# BSPD_Test_Board.net
KiCad netlist of a schematic drawn in EAGLE
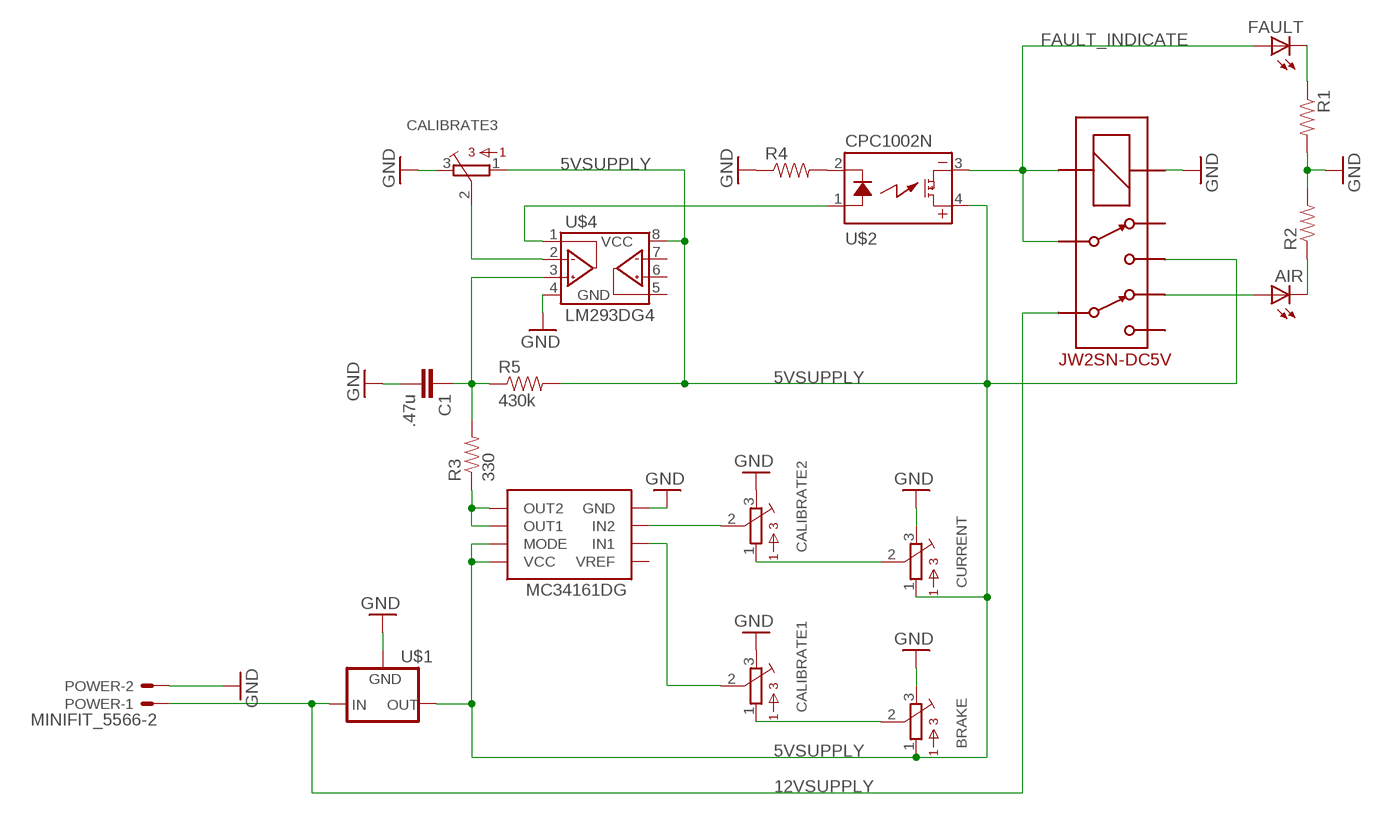
[diagram p0: schematic, sheet 1]

(export (version "E")
  (design (tool "Eeschema 10.0.6"))
  (components
    (comp (ref "AIR")
      (value "LED-5MM")
      (footprint "eagle-import:LED-5MM")
      (libsource (lib "eagle-import") (part "LED-5MM"))
    )
    (comp (ref "BRAKE")
      (value "TRIMPOT_3296C")
      (footprint "eagle-import:TRIMPOT_3296")
      (libsource (lib "eagle-import") (part "TRIMPOT_3296C"))
    )
    (comp (ref "C1")
      (value ".47u")
      (footprint "eagle-import:CAP-PTH-SMALLEZ")
      (libsource (lib "eagle-import") (part "CAPEZ"))
    )
    (comp (ref "CALIBRATE1")
      (value "TRIMPOT_3296C")
      (footprint "eagle-import:TRIMPOT_3296")
      (libsource (lib "eagle-import") (part "TRIMPOT_3296C"))
    )
    (comp (ref "CALIBRATE2")
      (value "TRIMPOT_3296C")
      (footprint "eagle-import:TRIMPOT_3296")
      (libsource (lib "eagle-import") (part "TRIMPOT_3296C"))
    )
    (comp (ref "CALIBRATE3")
      (value "TRIMPOT_3296C")
      (footprint "eagle-import:TRIMPOT_3296")
      (libsource (lib "eagle-import") (part "TRIMPOT_3296C"))
    )
    (comp (ref "CURRENT")
      (value "TRIMPOT_3296C")
      (footprint "eagle-import:TRIMPOT_3296")
      (libsource (lib "eagle-import") (part "TRIMPOT_3296C"))
    )
    (comp (ref "FAULT")
      (value "LED-5MM")
      (footprint "eagle-import:LED-5MM")
      (libsource (lib "eagle-import") (part "LED-5MM"))
    )
    (comp (ref "MC34161DG")
      (value "VOLTAGE_MONITOR_MC34161DG")
      (footprint "eagle-import:SOIC-08")
      (libsource (lib "eagle-import") (part "VOLTAGE_MONITOR_MC34161DG"))
    )
    (comp (ref "POWER")
      (value "MINIFIT_5566-2")
      (footprint "eagle-import:MINIFIT_5566-2")
      (libsource (lib "eagle-import") (part "MINIFIT_5566-2"))
    )
    (comp (ref "R1")
      (value "RESISTOR0805-RES")
      (footprint "eagle-import:0805")
      (libsource (lib "eagle-import") (part "RESISTOR0805-RES"))
    )
    (comp (ref "R2")
      (value "RESISTOR0805-RES")
      (footprint "eagle-import:0805")
      (libsource (lib "eagle-import") (part "RESISTOR0805-RES"))
    )
    (comp (ref "R3")
      (value "330")
      (footprint "eagle-import:0805")
      (libsource (lib "eagle-import") (part "RESISTOR0805-RES"))
    )
    (comp (ref "R4")
      (value "RESISTOR0805-RES")
      (footprint "eagle-import:0805")
      (libsource (lib "eagle-import") (part "RESISTOR0805-RES"))
    )
    (comp (ref "R5")
      (value "430k")
      (footprint "eagle-import:AXIAL-0.3EZ")
      (libsource (lib "eagle-import") (part "RESISTOREZ"))
    )
    (comp (ref "U$1")
      (value "5V_REGULATOR_LM340-NLM340MPX-5.0/NOPB")
      (footprint "eagle-import:SOT223")
      (libsource (lib "eagle-import") (part "5V_REGULATOR_LM340-NLM340MPX-5.0/NOPB"))
    )
    (comp (ref "U$2")
      (value "CPC1002N")
      (footprint "eagle-import:SOP04")
      (libsource (lib "eagle-import") (part "CPC1002N"))
    )
    (comp (ref "U$3")
      (value "DPDT_RELAY_PANASONIC_JW2SN-DC5V")
      (footprint "eagle-import:DPDT_RELAY_PANASONIC_JW2SN")
      (libsource (lib "eagle-import") (part "DPDT_RELAY_PANASONIC_JW2SN-DC5V"))
    )
    (comp (ref "U$4")
      (value "LM293DG4")
      (footprint "eagle-import:SOIC-08")
      (libsource (lib "eagle-import") (part "LM293DG4"))
    )
  )
  (nets
    (net (code "1") (name "/5VSUPPLY") (class "Default")
      (node (ref "BRAKE") (pin "1") (pinfunction "1_1") (pintype "passive"))
      (node (ref "CALIBRATE3") (pin "1") (pinfunction "1_1") (pintype "passive"))
      (node (ref "CURRENT") (pin "1") (pinfunction "1_1") (pintype "passive"))
      (node (ref "MC34161DG") (pin "7") (pinfunction "MODE_7") (pintype "passive"))
      (node (ref "MC34161DG") (pin "8") (pinfunction "VCC_8") (pintype "passive"))
      (node (ref "R5") (pin "P$2") (pinfunction "2_P$2") (pintype "passive"))
      (node (ref "U$1") (pin "3") (pinfunction "OUT_3") (pintype "output"))
      (node (ref "U$2") (pin "4") (pinfunction "DC+_4") (pintype "passive"))
      (node (ref "U$3") (pin "4") (pinfunction "4_4") (pintype "bidirectional"))
      (node (ref "U$4") (pin "8") (pinfunction "VCC_8") (pintype "passive"))
    )
    (net (code "2") (name "/12VSUPPLY") (class "Default")
      (node (ref "POWER") (pin "1") (pinfunction "S_1") (pintype "passive"))
      (node (ref "U$1") (pin "1") (pinfunction "IN_1") (pintype "input"))
      (node (ref "U$3") (pin "6") (pinfunction "6_6") (pintype "bidirectional"))
    )
    (net (code "3") (name "/FAULT_INDICATE") (class "Default")
      (node (ref "FAULT") (pin "A") (pinfunction "A_A") (pintype "passive"))
      (node (ref "U$2") (pin "3") (pinfunction "DC-_3") (pintype "passive"))
      (node (ref "U$3") (pin "3") (pinfunction "3_3") (pintype "bidirectional"))
      (node (ref "U$3") (pin "COIL-") (pinfunction "COIL-_COIL-") (pintype "bidirectional"))
    )
    (net (code "4") (name "GND") (class "Default")
      (node (ref "BRAKE") (pin "3") (pinfunction "3_3") (pintype "passive"))
      (node (ref "C1") (pin "2") (pinfunction "2_2") (pintype "passive"))
      (node (ref "CALIBRATE1") (pin "3") (pinfunction "3_3") (pintype "passive"))
      (node (ref "CALIBRATE2") (pin "3") (pinfunction "3_3") (pintype "passive"))
      (node (ref "CALIBRATE3") (pin "3") (pinfunction "3_3") (pintype "passive"))
      (node (ref "CURRENT") (pin "3") (pinfunction "3_3") (pintype "passive"))
      (node (ref "MC34161DG") (pin "4") (pinfunction "GND_4") (pintype "passive"))
      (node (ref "POWER") (pin "2") (pinfunction "S_2") (pintype "passive"))
      (node (ref "R1") (pin "2") (pinfunction "2_2") (pintype "passive"))
      (node (ref "R2") (pin "2") (pinfunction "2_2") (pintype "passive"))
      (node (ref "R4") (pin "1") (pinfunction "1_1") (pintype "passive"))
      (node (ref "U$1") (pin "2") (pinfunction "GND_2") (pintype "input"))
      (node (ref "U$1") (pin "4") (pinfunction "GND_4") (pintype "input"))
      (node (ref "U$3") (pin "COIL+") (pinfunction "COIL+_COIL+") (pintype "bidirectional"))
      (node (ref "U$4") (pin "4") (pinfunction "GND_4") (pintype "passive"))
    )
    (net (code "5") (name "Net-(AIR-C)") (class "Default")
      (node (ref "AIR") (pin "K") (pinfunction "C_K") (pintype "passive"))
      (node (ref "R2") (pin "1") (pinfunction "1_1") (pintype "passive"))
    )
    (net (code "6") (name "Net-(AIR-PadA)") (class "Default")
      (node (ref "AIR") (pin "A") (pinfunction "A_A") (pintype "passive"))
      (node (ref "U$3") (pin "7") (pinfunction "7_7") (pintype "bidirectional"))
    )
    (net (code "7") (name "Net-(BRAKE-Pad2)") (class "Default")
      (node (ref "BRAKE") (pin "2") (pinfunction "2_2") (pintype "passive"))
      (node (ref "CALIBRATE1") (pin "1") (pinfunction "1_1") (pintype "passive"))
    )
    (net (code "8") (name "Net-(CALIBRATE2-Pad1)") (class "Default")
      (node (ref "CALIBRATE2") (pin "1") (pinfunction "1_1") (pintype "passive"))
      (node (ref "CURRENT") (pin "2") (pinfunction "2_2") (pintype "passive"))
    )
    (net (code "9") (name "Net-(FAULT-C)") (class "Default")
      (node (ref "FAULT") (pin "K") (pinfunction "C_K") (pintype "passive"))
      (node (ref "R1") (pin "1") (pinfunction "1_1") (pintype "passive"))
    )
    (net (code "10") (name "Net-(MC34161DG-IN1)") (class "Default")
      (node (ref "CALIBRATE1") (pin "2") (pinfunction "2_2") (pintype "passive"))
      (node (ref "MC34161DG") (pin "2") (pinfunction "IN1_2") (pintype "passive"))
    )
    (net (code "11") (name "Net-(MC34161DG-IN2)") (class "Default")
      (node (ref "CALIBRATE2") (pin "2") (pinfunction "2_2") (pintype "passive"))
      (node (ref "MC34161DG") (pin "3") (pinfunction "IN2_3") (pintype "passive"))
    )
    (net (code "12") (name "Net-(MC34161DG-OUT1)") (class "Default")
      (node (ref "MC34161DG") (pin "5") (pinfunction "OUT2_5") (pintype "passive"))
      (node (ref "MC34161DG") (pin "6") (pinfunction "OUT1_6") (pintype "passive"))
      (node (ref "R3") (pin "1") (pinfunction "1_1") (pintype "passive"))
    )
    (net (code "13") (name "Net-(R5-1)") (class "Default")
      (node (ref "C1") (pin "1") (pinfunction "1_1") (pintype "passive"))
      (node (ref "R3") (pin "2") (pinfunction "2_2") (pintype "passive"))
      (node (ref "R5") (pin "P$1") (pinfunction "1_P$1") (pintype "passive"))
      (node (ref "U$4") (pin "3") (pinfunction "1IN+_3") (pintype "passive"))
    )
    (net (code "14") (name "Net-(U$2-CONTROL+)") (class "Default")
      (node (ref "U$2") (pin "1") (pinfunction "CONTROL+_1") (pintype "passive"))
      (node (ref "U$4") (pin "1") (pinfunction "1OUT_1") (pintype "passive"))
    )
    (net (code "15") (name "Net-(U$2-CONTROL-)") (class "Default")
      (node (ref "R4") (pin "2") (pinfunction "2_2") (pintype "passive"))
      (node (ref "U$2") (pin "2") (pinfunction "CONTROL-_2") (pintype "passive"))
    )
    (net (code "16") (name "Net-(U$4-1IN-)") (class "Default")
      (node (ref "CALIBRATE3") (pin "2") (pinfunction "2_2") (pintype "passive"))
      (node (ref "U$4") (pin "2") (pinfunction "1IN-_2") (pintype "passive"))
    )
    (net (code "17") (name "unconnected-(MC34161DG-VREF-Pad1)") (class "Default")
      (node (ref "MC34161DG") (pin "1") (pinfunction "VREF_1") (pintype "passive"))
    )
    (net (code "18") (name "unconnected-(U$3-Pad2)") (class "Default")
      (node (ref "U$3") (pin "2") (pinfunction "2_2") (pintype "bidirectional"))
    )
    (net (code "19") (name "unconnected-(U$3-Pad5)") (class "Default")
      (node (ref "U$3") (pin "5") (pinfunction "5_5") (pintype "bidirectional"))
    )
    (net (code "20") (name "unconnected-(U$4-2IN+-Pad5)") (class "Default")
      (node (ref "U$4") (pin "5") (pinfunction "2IN+_5") (pintype "passive"))
    )
    (net (code "21") (name "unconnected-(U$4-2IN--Pad6)") (class "Default")
      (node (ref "U$4") (pin "6") (pinfunction "2IN-_6") (pintype "passive"))
    )
    (net (code "22") (name "unconnected-(U$4-2OUT-Pad7)") (class "Default")
      (node (ref "U$4") (pin "7") (pinfunction "2OUT_7") (pintype "passive"))
    )
  )
)
